# BLE.net
KiCad netlist of a schematic drawn in Altium Designer
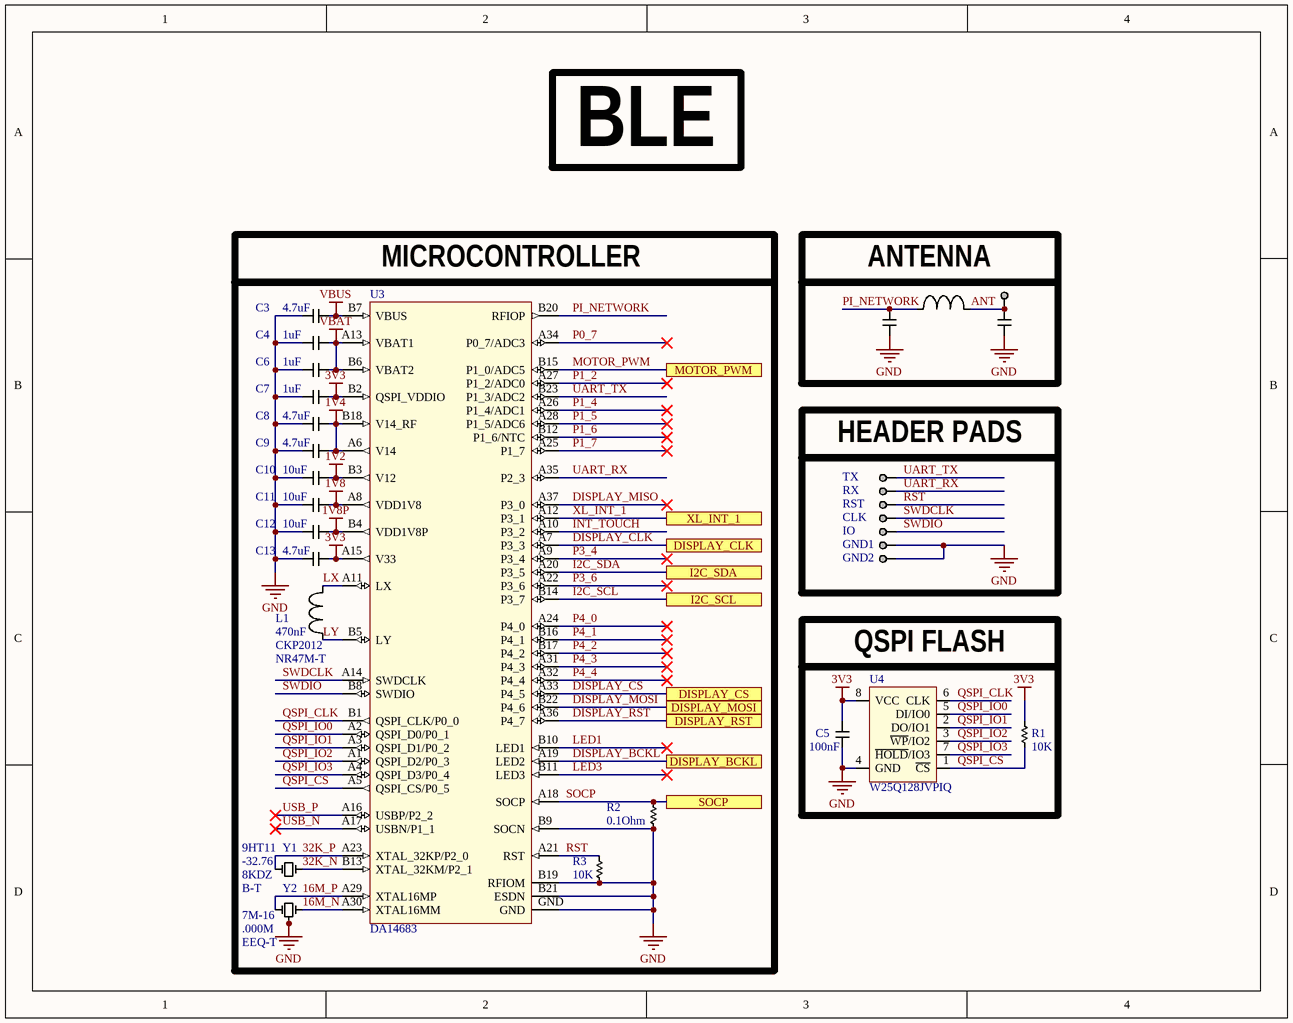
[diagram p0: BLE.SchDoc]

(export (version "E")
  (design (tool "Eeschema 10.0.6"))
  (components
    (comp (ref "ANT1")
      (value "0.1\" Header")
      (footprint "0.1\" Header")
      (libsource (lib "smLib") (part "0.1{dblquote} Header"))
    )
    (comp (ref "C3")
      (value "4.7uF")
      (footprint "CAP_0603_HIGH")
      (description "0603 Capacitor")
      (libsource (lib "smLib") (part "Capacitor_0603"))
    )
    (comp (ref "C4")
      (value "1uF")
      (footprint "CAP_0603_HIGH")
      (description "0603 Capacitor")
      (libsource (lib "smLib") (part "Capacitor_0603"))
    )
    (comp (ref "C5")
      (value "100nF")
      (footprint "CAP_0603_HIGH")
      (description "0603 Capacitor")
      (libsource (lib "smLib") (part "Capacitor_0603"))
    )
    (comp (ref "C6")
      (value "1uF")
      (footprint "CAP_0603_HIGH")
      (description "0603 Capacitor")
      (libsource (lib "smLib") (part "Capacitor_0603"))
    )
    (comp (ref "C7")
      (value "1uF")
      (footprint "CAP_0603_HIGH")
      (description "0603 Capacitor")
      (libsource (lib "smLib") (part "Capacitor_0603"))
    )
    (comp (ref "C8")
      (value "4.7uF")
      (footprint "CAP_0603_HIGH")
      (description "0603 Capacitor")
      (libsource (lib "smLib") (part "Capacitor_0603"))
    )
    (comp (ref "C9")
      (value "4.7uF")
      (footprint "CAP_0603_HIGH")
      (description "0603 Capacitor")
      (libsource (lib "smLib") (part "Capacitor_0603"))
    )
    (comp (ref "C10")
      (value "10uF")
      (footprint "CAP_0603_HIGH")
      (description "0603 Capacitor")
      (libsource (lib "smLib") (part "Capacitor_0603"))
    )
    (comp (ref "C11")
      (value "10uF")
      (footprint "CAP_0603_HIGH")
      (description "0603 Capacitor")
      (libsource (lib "smLib") (part "Capacitor_0603"))
    )
    (comp (ref "C12")
      (value "10uF")
      (footprint "CAP_0603_HIGH")
      (description "0603 Capacitor")
      (libsource (lib "smLib") (part "Capacitor_0603"))
    )
    (comp (ref "C13")
      (value "4.7uF")
      (footprint "CAP_0603_HIGH")
      (description "0603 Capacitor")
      (libsource (lib "smLib") (part "Capacitor_0603"))
    )
    (comp (ref "C16")
      (value "C")
      (footprint "CAP_0402_MEDIUM")
      (description "0402 Capacitor")
      (libsource (lib "smLib") (part "Capacitor_0402"))
    )
    (comp (ref "C17")
      (value "C")
      (footprint "CAP_0402_MEDIUM")
      (description "0402 Capacitor")
      (libsource (lib "smLib") (part "Capacitor_0402"))
    )
    (comp (ref "CLK")
      (value "0.1\" Pad")
      (footprint "0.1\" Pad")
      (libsource (lib "smLib") (part "0.1{dblquote} Pad"))
    )
    (comp (ref "GND1")
      (value "0.1\" Pad")
      (footprint "0.1\" Pad")
      (libsource (lib "smLib") (part "0.1{dblquote} Pad"))
    )
    (comp (ref "GND2")
      (value "0.1\" Pad")
      (footprint "0.1\" Pad")
      (libsource (lib "smLib") (part "0.1{dblquote} Pad"))
    )
    (comp (ref "IO")
      (value "0.1\" Pad")
      (footprint "0.1\" Pad")
      (libsource (lib "smLib") (part "0.1{dblquote} Pad"))
    )
    (comp (ref "L1")
      (value "470nF")
      (footprint "IND_0805_HIGH")
      (description "Inductor_0805")
      (fields
        (field (name "PARAMETER 1") "CKP2012")
        (field (name "PARAMETER 2") "NR47M-T")
        (field (name "Comment") "CKP2012NR47M-T")
      )
      (libsource (lib "smLib") (part "Inductor_0805"))
    )
    (comp (ref "L2")
      (value "L")
      (footprint "IND_0402_MEDIUM")
      (description "Inductor_0402")
      (libsource (lib "smLib") (part "Inductor_0402"))
    )
    (comp (ref "R1")
      (value "10K")
      (footprint "RES_0603_HIGH")
      (description "0603 Resistor")
      (libsource (lib "smLib") (part "Resistor_0603"))
    )
    (comp (ref "R2")
      (value "0.1Ohm")
      (footprint "RES_0603_HIGH")
      (description "0603 Resistor")
      (libsource (lib "smLib") (part "Resistor_0603"))
    )
    (comp (ref "R3")
      (value "10K")
      (footprint "RES_0603_HIGH")
      (description "0603 Resistor")
      (libsource (lib "smLib") (part "Resistor_0603"))
    )
    (comp (ref "RST")
      (value "0.1\" Pad")
      (footprint "0.1\" Pad")
      (libsource (lib "smLib") (part "0.1{dblquote} Pad"))
    )
    (comp (ref "RX")
      (value "0.1\" Pad")
      (footprint "0.1\" Pad")
      (libsource (lib "smLib") (part "0.1{dblquote} Pad"))
    )
    (comp (ref "TX")
      (value "0.1\" Pad")
      (footprint "0.1\" Pad")
      (libsource (lib "smLib") (part "0.1{dblquote} Pad"))
    )
    (comp (ref "U3")
      (value "DA14683")
      (footprint "DA14683")
      (description "SmartBond DA14683 Single-chip high-security Bluetooth 5 solution with expandable memory")
      (libsource (lib "smLib") (part "DA14683"))
    )
    (comp (ref "U4")
      (value "W25Q128JVPIQ")
      (footprint "W25Q128JVPIQ")
      (description "FLASH - NOR Memory IC 128Mb (16M x 8) SPI - Quad I/O, QPI, DTR 133MHz  8-WSON (6x5)")
      (libsource (lib "smLib") (part "W25Q128JVPIQ"))
    )
    (comp (ref "Y1")
      (value "9HT11-32.768KDZB-T")
      (footprint "9HT11-32.768KDZB-T")
      (description "32.768kHz ±20ppm Crystal 6pF 90 kOhms 2-SMD, No Lead")
      (fields
        (field (name "PARAMETER 1") "9HT11")
        (field (name "PARAMETER 2") "-32.76")
        (field (name "PARAMETER 3") "8KDZ")
        (field (name "PARAMETER 4") "B-T")
      )
      (libsource (lib "smLib") (part "9HT11-32.768KDZB-T"))
    )
    (comp (ref "Y2")
      (value "7M-16.000MEEQ-T")
      (footprint "7M-16.000MEEQ-T")
      (description "16MHz ±10ppm Crystal 10pF 80 Ohms 4-SMD, No Lead")
      (fields
        (field (name "PARAMETER 1") "7M-16")
        (field (name "PARAMETER 2") ".000M")
        (field (name "PARAMETER 3") "EEQ-T")
      )
      (libsource (lib "smLib") (part "7M-16.000MEEQ-T"))
    )
  )
  (nets
    (net (code "1") (name "/16M_N") (class "Default")
      (node (ref "U3") (pin "A30") (pinfunction "XTAL16MM_A30") (pintype "input"))
      (node (ref "Y2") (pin "3") (pinfunction "3_3") (pintype "passive"))
    )
    (net (code "2") (name "/16M_P") (class "Default")
      (node (ref "U3") (pin "A29") (pinfunction "XTAL16MP_A29") (pintype "input"))
      (node (ref "Y2") (pin "1") (pinfunction "1_1") (pintype "passive"))
    )
    (net (code "3") (name "/32K_N") (class "Default")
      (node (ref "U3") (pin "B13") (pinfunction "XTAL_32KM/P2_1_B13") (pintype "input"))
      (node (ref "Y1") (pin "2") (pinfunction "2_2") (pintype "passive"))
    )
    (net (code "4") (name "/32K_P") (class "Default")
      (node (ref "U3") (pin "A23") (pinfunction "XTAL_32KP/P2_0_A23") (pintype "input"))
      (node (ref "Y1") (pin "1") (pinfunction "1_1") (pintype "passive"))
    )
    (net (code "5") (name "/ANT") (class "Default")
      (node (ref "ANT1") (pin "1") (pinfunction "1_1") (pintype "passive"))
      (node (ref "C17") (pin "2") (pinfunction "2_2") (pintype "passive"))
      (node (ref "L2") (pin "1") (pinfunction "1_1") (pintype "passive"))
    )
    (net (code "6") (name "/DISPLAY_BCKL") (class "Default")
      (node (ref "U3") (pin "A19") (pinfunction "LED2_A19") (pintype "input"))
    )
    (net (code "7") (name "/DISPLAY_CLK") (class "Default")
      (node (ref "U3") (pin "A7") (pinfunction "P3_3_A7") (pintype "bidirectional"))
    )
    (net (code "8") (name "/DISPLAY_CS") (class "Default")
      (node (ref "U3") (pin "A33") (pinfunction "P4_5_A33") (pintype "bidirectional"))
    )
    (net (code "9") (name "/DISPLAY_MISO") (class "Default")
      (node (ref "U3") (pin "A37") (pinfunction "P3_0_A37") (pintype "bidirectional+no_connect"))
    )
    (net (code "10") (name "/DISPLAY_MOSI") (class "Default")
      (node (ref "U3") (pin "B22") (pinfunction "P4_6_B22") (pintype "bidirectional"))
    )
    (net (code "11") (name "/DISPLAY_RST") (class "Default")
      (node (ref "U3") (pin "A36") (pinfunction "P4_7_A36") (pintype "bidirectional"))
    )
    (net (code "12") (name "/I2C_SCL") (class "Default")
      (node (ref "U3") (pin "B14") (pinfunction "P3_7_B14") (pintype "bidirectional"))
    )
    (net (code "13") (name "/I2C_SDA") (class "Default")
      (node (ref "U3") (pin "A20") (pinfunction "P3_5_A20") (pintype "bidirectional"))
    )
    (net (code "14") (name "/INT_TOUCH") (class "Default")
      (node (ref "U3") (pin "A10") (pinfunction "P3_2_A10") (pintype "bidirectional"))
    )
    (net (code "15") (name "/LED1") (class "Default")
      (node (ref "U3") (pin "B10") (pinfunction "LED1_B10") (pintype "input+no_connect"))
    )
    (net (code "16") (name "/LED3") (class "Default")
      (node (ref "U3") (pin "B11") (pinfunction "LED3_B11") (pintype "input+no_connect"))
    )
    (net (code "17") (name "/LX") (class "Default")
      (node (ref "L1") (pin "2") (pinfunction "2_2") (pintype "passive"))
      (node (ref "U3") (pin "A11") (pinfunction "LX_A11") (pintype "bidirectional"))
    )
    (net (code "18") (name "/LY") (class "Default")
      (node (ref "L1") (pin "1") (pinfunction "1_1") (pintype "passive"))
      (node (ref "U3") (pin "B5") (pinfunction "LY_B5") (pintype "bidirectional"))
    )
    (net (code "19") (name "/MOTOR_PWM") (class "Default")
      (node (ref "U3") (pin "B15") (pinfunction "P1_0/ADC5_B15") (pintype "bidirectional"))
    )
    (net (code "20") (name "/P0_7") (class "Default")
      (node (ref "U3") (pin "A34") (pinfunction "P0_7/ADC3_A34") (pintype "bidirectional+no_connect"))
    )
    (net (code "21") (name "/P1_2") (class "Default")
      (node (ref "U3") (pin "A27") (pinfunction "P1_2/ADC0_A27") (pintype "bidirectional+no_connect"))
    )
    (net (code "22") (name "/P1_4") (class "Default")
      (node (ref "U3") (pin "A26") (pinfunction "P1_4/ADC1_A26") (pintype "bidirectional+no_connect"))
    )
    (net (code "23") (name "/P1_5") (class "Default")
      (node (ref "U3") (pin "A28") (pinfunction "P1_5/ADC6_A28") (pintype "bidirectional+no_connect"))
    )
    (net (code "24") (name "/P1_6") (class "Default")
      (node (ref "U3") (pin "B12") (pinfunction "P1_6/NTC_B12") (pintype "bidirectional+no_connect"))
    )
    (net (code "25") (name "/P1_7") (class "Default")
      (node (ref "U3") (pin "A25") (pinfunction "P1_7_A25") (pintype "bidirectional+no_connect"))
    )
    (net (code "26") (name "/P3_4") (class "Default")
      (node (ref "U3") (pin "A9") (pinfunction "P3_4_A9") (pintype "bidirectional+no_connect"))
    )
    (net (code "27") (name "/P3_6") (class "Default")
      (node (ref "U3") (pin "A22") (pinfunction "P3_6_A22") (pintype "bidirectional+no_connect"))
    )
    (net (code "28") (name "/P4_0") (class "Default")
      (node (ref "U3") (pin "A24") (pinfunction "P4_0_A24") (pintype "bidirectional+no_connect"))
    )
    (net (code "29") (name "/P4_1") (class "Default")
      (node (ref "U3") (pin "B16") (pinfunction "P4_1_B16") (pintype "bidirectional+no_connect"))
    )
    (net (code "30") (name "/P4_2") (class "Default")
      (node (ref "U3") (pin "B17") (pinfunction "P4_2_B17") (pintype "bidirectional+no_connect"))
    )
    (net (code "31") (name "/P4_3") (class "Default")
      (node (ref "U3") (pin "A31") (pinfunction "P4_3_A31") (pintype "bidirectional+no_connect"))
    )
    (net (code "32") (name "/P4_4") (class "Default")
      (node (ref "U3") (pin "A32") (pinfunction "P4_4_A32") (pintype "bidirectional+no_connect"))
    )
    (net (code "33") (name "/PI_NETWORK") (class "Default")
      (node (ref "C16") (pin "2") (pinfunction "2_2") (pintype "passive"))
      (node (ref "L2") (pin "2") (pinfunction "2_2") (pintype "passive"))
      (node (ref "U3") (pin "B20") (pinfunction "RFIOP_B20") (pintype "output"))
    )
    (net (code "34") (name "/QSPI_CLK") (class "Default")
      (node (ref "U3") (pin "B1") (pinfunction "QSPI_CLK/P0_0_B1") (pintype "output"))
      (node (ref "U4") (pin "6") (pinfunction "CLK_6") (pintype "passive"))
    )
    (net (code "35") (name "/QSPI_CS") (class "Default")
      (node (ref "R1") (pin "1") (pinfunction "1_1") (pintype "passive"))
      (node (ref "U3") (pin "A5") (pinfunction "QSPI_CS/P0_5_A5") (pintype "output"))
      (node (ref "U4") (pin "1") (pinfunction "~{CS}_1") (pintype "passive"))
    )
    (net (code "36") (name "/QSPI_IO0") (class "Default")
      (node (ref "U3") (pin "A2") (pinfunction "QSPI_D0/P0_1_A2") (pintype "bidirectional"))
      (node (ref "U4") (pin "5") (pinfunction "DI/IO0_5") (pintype "passive"))
    )
    (net (code "37") (name "/QSPI_IO1") (class "Default")
      (node (ref "U3") (pin "A3") (pinfunction "QSPI_D1/P0_2_A3") (pintype "bidirectional"))
      (node (ref "U4") (pin "2") (pinfunction "DO/IO1_2") (pintype "passive"))
    )
    (net (code "38") (name "/QSPI_IO2") (class "Default")
      (node (ref "U3") (pin "A1") (pinfunction "QSPI_D2/P0_3_A1") (pintype "bidirectional"))
      (node (ref "U4") (pin "3") (pinfunction "~{WP}/IO2_3") (pintype "passive"))
    )
    (net (code "39") (name "/QSPI_IO3") (class "Default")
      (node (ref "U3") (pin "A4") (pinfunction "QSPI_D3/P0_4_A4") (pintype "bidirectional"))
      (node (ref "U4") (pin "7") (pinfunction "~{HOLD}/IO3_7") (pintype "passive"))
    )
    (net (code "40") (name "/RST") (class "Default")
      (node (ref "R3") (pin "2") (pinfunction "2_2") (pintype "passive"))
      (node (ref "RST") (pin "1") (pinfunction "1_1") (pintype "passive"))
      (node (ref "U3") (pin "A21") (pinfunction "RST_A21") (pintype "input"))
    )
    (net (code "41") (name "/SOCP") (class "Default")
      (node (ref "R2") (pin "2") (pinfunction "2_2") (pintype "passive"))
      (node (ref "U3") (pin "A18") (pinfunction "SOCP_A18") (pintype "input"))
    )
    (net (code "42") (name "/SWDCLK") (class "Default")
      (node (ref "CLK") (pin "1") (pinfunction "1_1") (pintype "passive"))
      (node (ref "U3") (pin "A14") (pinfunction "SWDCLK_A14") (pintype "input"))
    )
    (net (code "43") (name "/SWDIO") (class "Default")
      (node (ref "IO") (pin "1") (pinfunction "1_1") (pintype "passive"))
      (node (ref "U3") (pin "B8") (pinfunction "SWDIO_B8") (pintype "bidirectional"))
    )
    (net (code "44") (name "/UART_RX") (class "Default")
      (node (ref "RX") (pin "1") (pinfunction "1_1") (pintype "passive"))
      (node (ref "U3") (pin "A35") (pinfunction "P2_3_A35") (pintype "bidirectional"))
    )
    (net (code "45") (name "/UART_TX") (class "Default")
      (node (ref "TX") (pin "1") (pinfunction "1_1") (pintype "passive"))
      (node (ref "U3") (pin "B23") (pinfunction "P1_3/ADC2_B23") (pintype "bidirectional"))
    )
    (net (code "46") (name "/USB_N") (class "Default")
      (node (ref "U3") (pin "A17") (pinfunction "USBN/P1_1_A17") (pintype "bidirectional+no_connect"))
    )
    (net (code "47") (name "/USB_P") (class "Default")
      (node (ref "U3") (pin "A16") (pinfunction "USBP/P2_2_A16") (pintype "bidirectional+no_connect"))
    )
    (net (code "48") (name "/XL_INT_1") (class "Default")
      (node (ref "U3") (pin "A12") (pinfunction "P3_1_A12") (pintype "bidirectional"))
    )
    (net (code "49") (name "1V2") (class "Default")
      (node (ref "C10") (pin "1") (pinfunction "1_1") (pintype "passive"))
      (node (ref "U3") (pin "B3") (pinfunction "V12_B3") (pintype "output"))
    )
    (net (code "50") (name "1V4") (class "Default")
      (node (ref "C8") (pin "1") (pinfunction "1_1") (pintype "passive"))
      (node (ref "C9") (pin "1") (pinfunction "1_1") (pintype "passive"))
      (node (ref "U3") (pin "A6") (pinfunction "V14_A6") (pintype "output"))
      (node (ref "U3") (pin "B18") (pinfunction "V14_RF_B18") (pintype "input"))
    )
    (net (code "51") (name "1V8") (class "Default")
      (node (ref "C11") (pin "1") (pinfunction "1_1") (pintype "passive"))
      (node (ref "U3") (pin "A8") (pinfunction "VDD1V8_A8") (pintype "output"))
    )
    (net (code "52") (name "1V8P") (class "Default")
      (node (ref "C12") (pin "1") (pinfunction "1_1") (pintype "passive"))
      (node (ref "U3") (pin "B4") (pinfunction "VDD1V8P_B4") (pintype "output"))
    )
    (net (code "53") (name "3V3") (class "Default")
      (node (ref "C13") (pin "1") (pinfunction "1_1") (pintype "passive"))
      (node (ref "C5") (pin "1") (pinfunction "1_1") (pintype "passive"))
      (node (ref "C7") (pin "1") (pinfunction "1_1") (pintype "passive"))
      (node (ref "R1") (pin "2") (pinfunction "2_2") (pintype "passive"))
      (node (ref "U3") (pin "A15") (pinfunction "V33_A15") (pintype "output"))
      (node (ref "U3") (pin "B2") (pinfunction "QSPI_VDDIO_B2") (pintype "input"))
      (node (ref "U4") (pin "8") (pinfunction "VCC_8") (pintype "passive"))
    )
    (net (code "54") (name "GND") (class "Default")
      (node (ref "C10") (pin "2") (pinfunction "2_2") (pintype "passive"))
      (node (ref "C11") (pin "2") (pinfunction "2_2") (pintype "passive"))
      (node (ref "C12") (pin "2") (pinfunction "2_2") (pintype "passive"))
      (node (ref "C13") (pin "2") (pinfunction "2_2") (pintype "passive"))
      (node (ref "C16") (pin "1") (pinfunction "1_1") (pintype "passive"))
      (node (ref "C17") (pin "1") (pinfunction "1_1") (pintype "passive"))
      (node (ref "C3") (pin "2") (pinfunction "2_2") (pintype "passive"))
      (node (ref "C4") (pin "2") (pinfunction "2_2") (pintype "passive"))
      (node (ref "C5") (pin "2") (pinfunction "2_2") (pintype "passive"))
      (node (ref "C6") (pin "2") (pinfunction "2_2") (pintype "passive"))
      (node (ref "C7") (pin "2") (pinfunction "2_2") (pintype "passive"))
      (node (ref "C8") (pin "2") (pinfunction "2_2") (pintype "passive"))
      (node (ref "C9") (pin "2") (pinfunction "2_2") (pintype "passive"))
      (node (ref "GND1") (pin "1") (pinfunction "1_1") (pintype "passive"))
      (node (ref "GND2") (pin "1") (pinfunction "1_1") (pintype "passive"))
      (node (ref "R2") (pin "1") (pinfunction "1_1") (pintype "passive"))
      (node (ref "R3") (pin "1") (pinfunction "1_1") (pintype "passive"))
      (node (ref "U3") (pin "B19") (pinfunction "RFIOM_B19") (pintype "power_in"))
      (node (ref "U3") (pin "B21") (pinfunction "ESDN_B21") (pintype "power_in"))
      (node (ref "U3") (pin "B9") (pinfunction "SOCN_B9") (pintype "input"))
      (node (ref "U3") (pin "GND") (pinfunction "GND_GND") (pintype "power_in"))
      (node (ref "U4") (pin "4") (pinfunction "GND_4") (pintype "passive"))
      (node (ref "Y2") (pin "2") (pinfunction "2_2") (pintype "passive"))
      (node (ref "Y2") (pin "4") (pinfunction "4_4") (pintype "passive"))
    )
    (net (code "55") (name "VBAT") (class "Default")
      (node (ref "C4") (pin "1") (pinfunction "1_1") (pintype "passive"))
      (node (ref "C6") (pin "1") (pinfunction "1_1") (pintype "passive"))
      (node (ref "U3") (pin "A13") (pinfunction "VBAT1_A13") (pintype "input"))
      (node (ref "U3") (pin "B6") (pinfunction "VBAT2_B6") (pintype "input"))
    )
    (net (code "56") (name "VBUS") (class "Default")
      (node (ref "C3") (pin "1") (pinfunction "1_1") (pintype "passive"))
      (node (ref "U3") (pin "B7") (pinfunction "VBUS_B7") (pintype "input"))
    )
  )
)
